# MSP430F149.net
KiCad netlist of a schematic drawn in Altium Designer
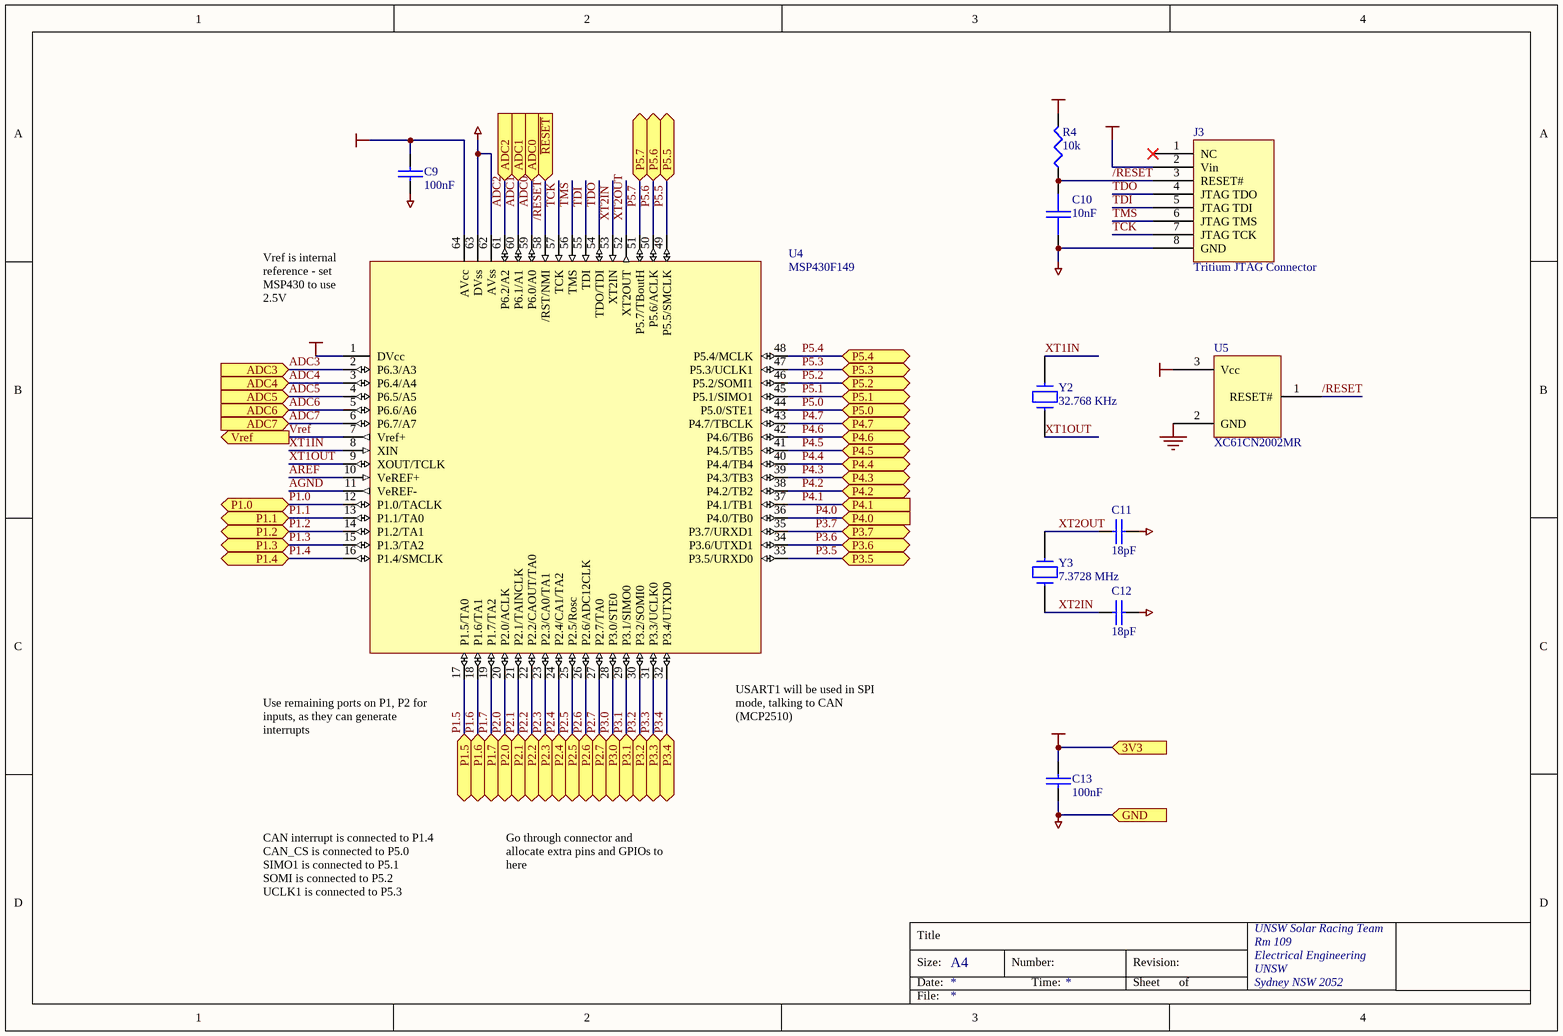
[diagram p0: MSP430F149.SCHDOC]

(export (version "E")
  (design (tool "Eeschema 10.0.6"))
  (components
    (comp (ref "C9")
      (value "100nF")
      (footprint "0603")
      (description "Capacitor")
      (libsource (lib "*") (part "CAP"))
    )
    (comp (ref "C10")
      (value "10nF")
      (footprint "0603")
      (description "Capacitor")
      (libsource (lib "SunswiftLib20030312RR") (part "CAP"))
    )
    (comp (ref "C11")
      (value "18pF")
      (footprint "0603")
      (description "Capacitor")
      (libsource (lib "*") (part "CAP"))
    )
    (comp (ref "C12")
      (value "18pF")
      (footprint "0603")
      (description "Capacitor")
      (libsource (lib "*") (part "CAP"))
    )
    (comp (ref "C13")
      (value "100nF")
      (footprint "0603")
      (description "Capacitor")
      (libsource (lib "*") (part "CAP"))
    )
    (comp (ref "J3")
      (value "Tritium JTAG Connector")
      (footprint "IDC10")
      (description "Tritium JTAG interface for MSP430")
      (libsource (lib "SunswiftLib20030312RR") (part "430F_JTAG_TRITIUM"))
    )
    (comp (ref "R4")
      (value "10k")
      (footprint "0603")
      (description "Resistor")
      (libsource (lib "SunswiftLib20030312RR") (part "RES1"))
    )
    (comp (ref "U4")
      (value "MSP430F149")
      (footprint "QFP64")
      (libsource (lib "SunswiftLib20030312RR") (part "MSP430F14X"))
    )
    (comp (ref "U5")
      (value "XC61CN2002MR")
      (footprint "SOT23(3)")
      (description "SOT23 reset generator")
      (libsource (lib "*") (part "XC61F"))
    )
    (comp (ref "Y2")
      (value "32.768 KHz")
      (footprint "WATCHA")
      (description "Crystal")
      (libsource (lib "*") (part "CRYSTAL"))
    )
    (comp (ref "Y3")
      (value "7.3728 MHz")
      (footprint "HC49/4H")
      (description "Crystal")
      (libsource (lib "*") (part "CRYSTAL"))
    )
  )
  (nets
    (net (code "1") (name "/ADC0") (class "Default")
      (node (ref "U4") (pin "59") (pinfunction "P6.0/A0_59") (pintype "bidirectional"))
    )
    (net (code "2") (name "/ADC1") (class "Default")
      (node (ref "U4") (pin "60") (pinfunction "P6.1/A1_60") (pintype "bidirectional"))
    )
    (net (code "3") (name "/ADC2") (class "Default")
      (node (ref "U4") (pin "61") (pinfunction "P6.2/A2_61") (pintype "bidirectional"))
    )
    (net (code "4") (name "/ADC3") (class "Default")
      (node (ref "U4") (pin "2") (pinfunction "P6.3/A3_2") (pintype "bidirectional"))
    )
    (net (code "5") (name "/ADC4") (class "Default")
      (node (ref "U4") (pin "3") (pinfunction "P6.4/A4_3") (pintype "bidirectional"))
    )
    (net (code "6") (name "/ADC5") (class "Default")
      (node (ref "U4") (pin "4") (pinfunction "P6.5/A5_4") (pintype "bidirectional"))
    )
    (net (code "7") (name "/ADC6") (class "Default")
      (node (ref "U4") (pin "5") (pinfunction "P6.6/A6_5") (pintype "bidirectional"))
    )
    (net (code "8") (name "/ADC7") (class "Default")
      (node (ref "U4") (pin "6") (pinfunction "P6.7/A7_6") (pintype "bidirectional"))
    )
    (net (code "9") (name "/AGND") (class "Default")
      (node (ref "U4") (pin "11") (pinfunction "VeREF-_11") (pintype "output"))
    )
    (net (code "10") (name "/AREF") (class "Default")
      (node (ref "U4") (pin "10") (pinfunction "VeREF+_10") (pintype "input"))
    )
    (net (code "11") (name "/P1.0") (class "Default")
      (node (ref "U4") (pin "12") (pinfunction "P1.0/TACLK_12") (pintype "bidirectional"))
    )
    (net (code "12") (name "/P1.1") (class "Default")
      (node (ref "U4") (pin "13") (pinfunction "P1.1/TA0_13") (pintype "bidirectional"))
    )
    (net (code "13") (name "/P1.2") (class "Default")
      (node (ref "U4") (pin "14") (pinfunction "P1.2/TA1_14") (pintype "bidirectional"))
    )
    (net (code "14") (name "/P1.3") (class "Default")
      (node (ref "U4") (pin "15") (pinfunction "P1.3/TA2_15") (pintype "bidirectional"))
    )
    (net (code "15") (name "/P1.4") (class "Default")
      (node (ref "U4") (pin "16") (pinfunction "P1.4/SMCLK_16") (pintype "bidirectional"))
    )
    (net (code "16") (name "/P1.5") (class "Default")
      (node (ref "U4") (pin "17") (pinfunction "P1.5/TA0_17") (pintype "bidirectional"))
    )
    (net (code "17") (name "/P1.6") (class "Default")
      (node (ref "U4") (pin "18") (pinfunction "P1.6/TA1_18") (pintype "bidirectional"))
    )
    (net (code "18") (name "/P1.7") (class "Default")
      (node (ref "U4") (pin "19") (pinfunction "P1.7/TA2_19") (pintype "bidirectional"))
    )
    (net (code "19") (name "/P2.0") (class "Default")
      (node (ref "U4") (pin "20") (pinfunction "P2.0/ACLK_20") (pintype "bidirectional"))
    )
    (net (code "20") (name "/P2.1") (class "Default")
      (node (ref "U4") (pin "21") (pinfunction "P2.1/TAINCLK_21") (pintype "bidirectional"))
    )
    (net (code "21") (name "/P2.2") (class "Default")
      (node (ref "U4") (pin "22") (pinfunction "P2.2/CAOUT/TA0_22") (pintype "bidirectional"))
    )
    (net (code "22") (name "/P2.3") (class "Default")
      (node (ref "U4") (pin "23") (pinfunction "P2.3/CA0/TA1_23") (pintype "bidirectional"))
    )
    (net (code "23") (name "/P2.4") (class "Default")
      (node (ref "U4") (pin "24") (pinfunction "P2.4/CA1/TA2_24") (pintype "bidirectional"))
    )
    (net (code "24") (name "/P2.5") (class "Default")
      (node (ref "U4") (pin "25") (pinfunction "P2.5/Rosc_25") (pintype "bidirectional"))
    )
    (net (code "25") (name "/P2.6") (class "Default")
      (node (ref "U4") (pin "26") (pinfunction "P2.6/ADC12CLK_26") (pintype "bidirectional"))
    )
    (net (code "26") (name "/P2.7") (class "Default")
      (node (ref "U4") (pin "27") (pinfunction "P2.7/TA0_27") (pintype "bidirectional"))
    )
    (net (code "27") (name "/P3.0") (class "Default")
      (node (ref "U4") (pin "28") (pinfunction "P3.0/STE0_28") (pintype "bidirectional"))
    )
    (net (code "28") (name "/P3.1") (class "Default")
      (node (ref "U4") (pin "29") (pinfunction "P3.1/SIMO0_29") (pintype "bidirectional"))
    )
    (net (code "29") (name "/P3.2") (class "Default")
      (node (ref "U4") (pin "30") (pinfunction "P3.2/SOMI0_30") (pintype "bidirectional"))
    )
    (net (code "30") (name "/P3.3") (class "Default")
      (node (ref "U4") (pin "31") (pinfunction "P3.3/UCLK0_31") (pintype "bidirectional"))
    )
    (net (code "31") (name "/P3.4") (class "Default")
      (node (ref "U4") (pin "32") (pinfunction "P3.4/UTXD0_32") (pintype "bidirectional"))
    )
    (net (code "32") (name "/P3.5") (class "Default")
      (node (ref "U4") (pin "33") (pinfunction "P3.5/URXD0_33") (pintype "bidirectional"))
    )
    (net (code "33") (name "/P3.6") (class "Default")
      (node (ref "U4") (pin "34") (pinfunction "P3.6/UTXD1_34") (pintype "bidirectional"))
    )
    (net (code "34") (name "/P3.7") (class "Default")
      (node (ref "U4") (pin "35") (pinfunction "P3.7/URXD1_35") (pintype "bidirectional"))
    )
    (net (code "35") (name "/P4.0") (class "Default")
      (node (ref "U4") (pin "36") (pinfunction "P4.0/TB0_36") (pintype "bidirectional"))
    )
    (net (code "36") (name "/P4.1") (class "Default")
      (node (ref "U4") (pin "37") (pinfunction "P4.1/TB1_37") (pintype "bidirectional"))
    )
    (net (code "37") (name "/P4.2") (class "Default")
      (node (ref "U4") (pin "38") (pinfunction "P4.2/TB2_38") (pintype "bidirectional"))
    )
    (net (code "38") (name "/P4.3") (class "Default")
      (node (ref "U4") (pin "39") (pinfunction "P4.3/TB3_39") (pintype "bidirectional"))
    )
    (net (code "39") (name "/P4.4") (class "Default")
      (node (ref "U4") (pin "40") (pinfunction "P4.4/TB4_40") (pintype "bidirectional"))
    )
    (net (code "40") (name "/P4.5") (class "Default")
      (node (ref "U4") (pin "41") (pinfunction "P4.5/TB5_41") (pintype "bidirectional"))
    )
    (net (code "41") (name "/P4.6") (class "Default")
      (node (ref "U4") (pin "42") (pinfunction "P4.6/TB6_42") (pintype "bidirectional"))
    )
    (net (code "42") (name "/P4.7") (class "Default")
      (node (ref "U4") (pin "43") (pinfunction "P4.7/TBCLK_43") (pintype "bidirectional"))
    )
    (net (code "43") (name "/P5.0") (class "Default")
      (node (ref "U4") (pin "44") (pinfunction "P5.0/STE1_44") (pintype "bidirectional"))
    )
    (net (code "44") (name "/P5.1") (class "Default")
      (node (ref "U4") (pin "45") (pinfunction "P5.1/SIMO1_45") (pintype "bidirectional"))
    )
    (net (code "45") (name "/P5.2") (class "Default")
      (node (ref "U4") (pin "46") (pinfunction "P5.2/SOMI1_46") (pintype "bidirectional"))
    )
    (net (code "46") (name "/P5.3") (class "Default")
      (node (ref "U4") (pin "47") (pinfunction "P5.3/UCLK1_47") (pintype "bidirectional"))
    )
    (net (code "47") (name "/P5.4") (class "Default")
      (node (ref "U4") (pin "48") (pinfunction "P5.4/MCLK_48") (pintype "bidirectional"))
    )
    (net (code "48") (name "/P5.5") (class "Default")
      (node (ref "U4") (pin "49") (pinfunction "P5.5/SMCLK_49") (pintype "bidirectional"))
    )
    (net (code "49") (name "/P5.6") (class "Default")
      (node (ref "U4") (pin "50") (pinfunction "P5.6/ACLK_50") (pintype "bidirectional"))
    )
    (net (code "50") (name "/P5.7") (class "Default")
      (node (ref "U4") (pin "51") (pinfunction "P5.7/TBoutH_51") (pintype "bidirectional"))
    )
    (net (code "51") (name "/TCK") (class "Default")
      (node (ref "J3") (pin "7") (pinfunction "JTAG_TCK_7") (pintype "passive"))
      (node (ref "U4") (pin "57") (pinfunction "TCK_57") (pintype "input"))
    )
    (net (code "52") (name "/TDI") (class "Default")
      (node (ref "J3") (pin "5") (pinfunction "JTAG_TDI_5") (pintype "passive"))
      (node (ref "U4") (pin "55") (pinfunction "TDI_55") (pintype "input"))
    )
    (net (code "53") (name "/TDO") (class "Default")
      (node (ref "J3") (pin "4") (pinfunction "JTAG_TDO_4") (pintype "passive"))
      (node (ref "U4") (pin "54") (pinfunction "TDO/TDI_54") (pintype "bidirectional"))
    )
    (net (code "54") (name "/TMS") (class "Default")
      (node (ref "J3") (pin "6") (pinfunction "JTAG_TMS_6") (pintype "passive"))
      (node (ref "U4") (pin "56") (pinfunction "TMS_56") (pintype "input"))
    )
    (net (code "55") (name "/Vref") (class "Default")
      (node (ref "U4") (pin "7") (pinfunction "Vref+_7") (pintype "output"))
    )
    (net (code "56") (name "/XT1IN") (class "Default")
      (node (ref "U4") (pin "8") (pinfunction "XIN_8") (pintype "input"))
      (node (ref "Y2") (pin "2") (pinfunction "2_2") (pintype "passive"))
    )
    (net (code "57") (name "/XT1OUT") (class "Default")
      (node (ref "U4") (pin "9") (pinfunction "XOUT/TCLK_9") (pintype "bidirectional"))
      (node (ref "Y2") (pin "1") (pinfunction "1_1") (pintype "passive"))
    )
    (net (code "58") (name "/XT2IN") (class "Default")
      (node (ref "C12") (pin "1") (pinfunction "1_1") (pintype "passive"))
      (node (ref "U4") (pin "53") (pinfunction "XT2IN_53") (pintype "input"))
      (node (ref "Y3") (pin "1") (pinfunction "1_1") (pintype "passive"))
    )
    (net (code "59") (name "/XT2OUT") (class "Default")
      (node (ref "C11") (pin "1") (pinfunction "1_1") (pintype "passive"))
      (node (ref "U4") (pin "52") (pinfunction "XT2OUT_52") (pintype "output"))
      (node (ref "Y3") (pin "2") (pinfunction "2_2") (pintype "passive"))
    )
    (net (code "60") (name "/{slash}RESET") (class "Default")
      (node (ref "C10") (pin "1") (pinfunction "1_1") (pintype "passive"))
      (node (ref "J3") (pin "3") (pinfunction "RESET#_3") (pintype "passive"))
      (node (ref "R4") (pin "1") (pinfunction "1_1") (pintype "passive"))
      (node (ref "U4") (pin "58") (pinfunction "/RST/NMI_58") (pintype "input"))
      (node (ref "U5") (pin "1") (pinfunction "RESET#_1") (pintype "passive"))
    )
    (net (code "61") (name "3V3") (class "Default")
      (node (ref "C13") (pin "1") (pinfunction "1_1") (pintype "passive"))
      (node (ref "C9") (pin "1") (pinfunction "1_1") (pintype "passive"))
      (node (ref "J3") (pin "2") (pinfunction "Vin_2") (pintype "passive"))
      (node (ref "R4") (pin "2") (pinfunction "2_2") (pintype "passive"))
      (node (ref "U4") (pin "1") (pinfunction "DVcc_1") (pintype "power_in"))
      (node (ref "U4") (pin "64") (pinfunction "AVcc_64") (pintype "power_in"))
      (node (ref "U5") (pin "3") (pinfunction "Vcc_3") (pintype "passive"))
    )
    (net (code "62") (name "GND") (class "Default")
      (node (ref "C10") (pin "2") (pinfunction "2_2") (pintype "passive"))
      (node (ref "C11") (pin "2") (pinfunction "2_2") (pintype "passive"))
      (node (ref "C12") (pin "2") (pinfunction "2_2") (pintype "passive"))
      (node (ref "C13") (pin "2") (pinfunction "2_2") (pintype "passive"))
      (node (ref "C9") (pin "2") (pinfunction "2_2") (pintype "passive"))
      (node (ref "J3") (pin "8") (pinfunction "GND_8") (pintype "passive"))
      (node (ref "U4") (pin "62") (pinfunction "AVss_62") (pintype "power_in"))
      (node (ref "U4") (pin "63") (pinfunction "DVss_63") (pintype "power_in"))
      (node (ref "U5") (pin "2") (pinfunction "GND_2") (pintype "passive"))
    )
    (net (code "63") (name "unconnected-(J3-NC-Pad1)") (class "Default")
      (node (ref "J3") (pin "1") (pinfunction "NC_1") (pintype "passive+no_connect"))
    )
  )
)
